# EEPROM.net
KiCad netlist of a schematic drawn in Altium Designer
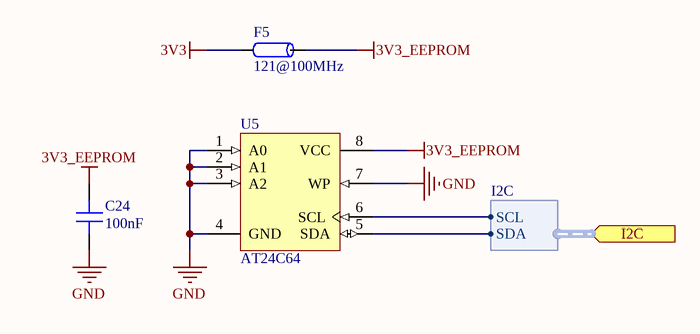
[diagram p0: EEPROM.SchDoc]

(export (version "E")
  (design (tool "Eeschema 10.0.6"))
  (components
    (comp (ref "C24")
      (value "100nF")
      (footprint "CAP 0603_1608")
      (description "SMT Capacitor")
      (libsource (lib "Capacitor") (part "Cap 0603"))
    )
    (comp (ref "F5")
      (value "121@100MHz")
      (footprint "Ferrite-0805")
      (description "Ferrite Bead")
      (libsource (lib "Salman_lib") (part "Ferrite Bead"))
    )
    (comp (ref "U5")
      (value "AT24C64")
      (footprint "TSSOP-8 3X4.4MM P0.65MM")
      (description "EEPROM Memory IC 64Kb (8K x 8) I²C 400kHz 900ns 8-TSSOP")
      (fields (field (name "PARTNUMBER") "AT24C64B-10TU-1.8"))
      (libsource (lib "Chip") (part "AT24C64 (SMD TSSOP)"))
    )
  )
  (nets
    (net (code "2") (name "/SCL") (class "Default")
      (node (ref "U5") (pin "6") (pinfunction "SCL_6") (pintype "input"))
    )
    (net (code "3") (name "/SDA") (class "Default")
      (node (ref "U5") (pin "5") (pinfunction "SDA_5") (pintype "bidirectional"))
    )
    (net (code "5") (name "3V3") (class "Default")
      (node (ref "F5") (pin "1") (pinfunction "67_1") (pintype "passive"))
    )
    (net (code "6") (name "3V3_EEPROM") (class "Default")
      (node (ref "C24") (pin "2") (pinfunction "2_2") (pintype "passive"))
      (node (ref "F5") (pin "2") (pinfunction "66_2") (pintype "passive"))
      (node (ref "U5") (pin "8") (pinfunction "VCC_8") (pintype "power_in"))
    )
    (net (code "7") (name "GND") (class "Default")
      (node (ref "C24") (pin "1") (pinfunction "1_1") (pintype "passive"))
      (node (ref "U5") (pin "1") (pinfunction "A0_1") (pintype "input"))
      (node (ref "U5") (pin "2") (pinfunction "A1_2") (pintype "input"))
      (node (ref "U5") (pin "3") (pinfunction "A2_3") (pintype "input"))
      (node (ref "U5") (pin "4") (pinfunction "GND_4") (pintype "power_in"))
      (node (ref "U5") (pin "7") (pinfunction "WP_7") (pintype "input"))
    )
  )
)
